# 06_KEY.net
KiCad netlist of a schematic drawn in Altium Designer
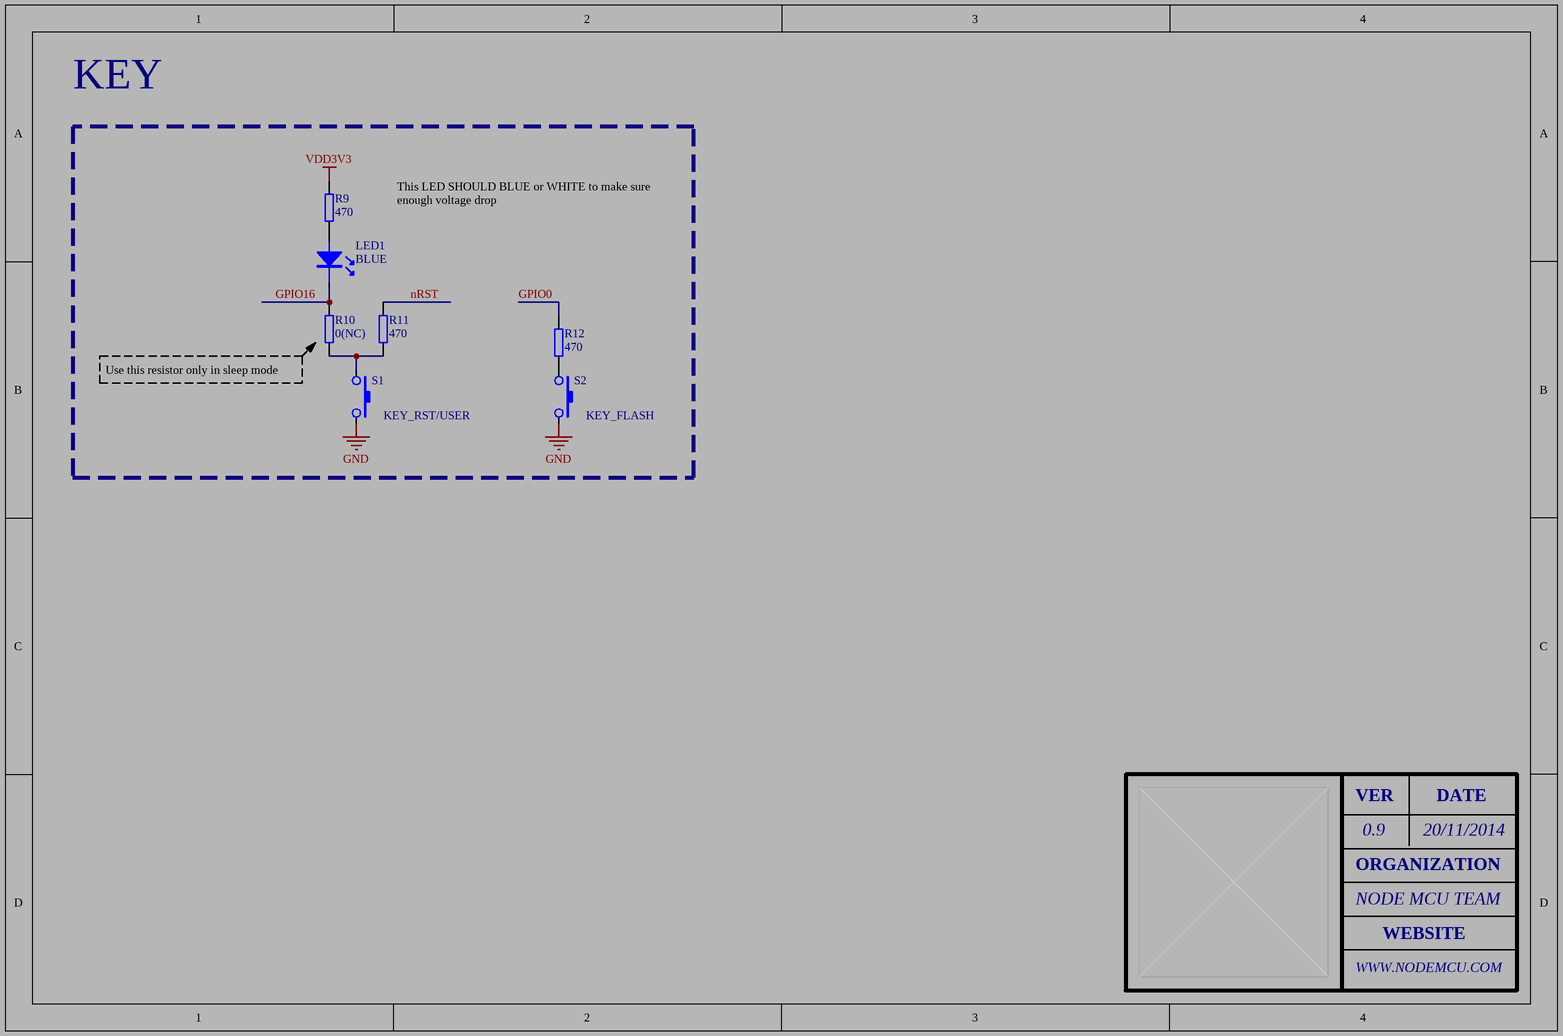
[diagram p0: 06_KEY.SchDoc]

(export (version "E")
  (design (tool "Eeschema 10.0.6"))
  (components
    (comp (ref "LED1")
      (value "BLUE")
      (footprint "SMT_LED_0603")
      (description "SMT LED")
      (libsource (lib "Vowstar_Basic_Device") (part "SMT_LED_0603"))
    )
    (comp (ref "R9")
      (value "470")
      (footprint "SMT_R_0402")
      (description "Surface mount resistor 0402")
      (libsource (lib "Vowstar_Basic_Device") (part "SMT_R_0402"))
    )
    (comp (ref "R10")
      (value "0(NC)")
      (footprint "SMT_R_0402")
      (description "Surface mount resistor 0402")
      (libsource (lib "Vowstar_Basic_Device") (part "SMT_R_0402"))
    )
    (comp (ref "R11")
      (value "470")
      (footprint "SMT_R_0402")
      (description "Surface mount resistor 0402")
      (libsource (lib "Vowstar_Basic_Device") (part "SMT_R_0402"))
    )
    (comp (ref "R12")
      (value "470")
      (footprint "SMT_R_0402")
      (description "Surface mount resistor 0402")
      (libsource (lib "Vowstar_Basic_Device") (part "SMT_R_0402"))
    )
    (comp (ref "S1")
      (value "KEY_RST/USER")
      (footprint "SMT_SW_PTS_820")
      (description "SMT Tactile ‎Switch PTS 820 Series")
      (libsource (lib "Vowstar_Switch") (part "SMT_SW_PTS_820"))
    )
    (comp (ref "S2")
      (value "KEY_FLASH")
      (footprint "SMT_SW_PTS_820")
      (description "SMT Tactile ‎Switch PTS 820 Series")
      (libsource (lib "Vowstar_Switch") (part "SMT_SW_PTS_820"))
    )
  )
  (nets
    (net (code "1") (name "/GPIO0") (class "Default")
      (node (ref "R12") (pin "2") (pinfunction "2_2") (pintype "passive"))
    )
    (net (code "2") (name "/GPIO16") (class "Default")
      (node (ref "LED1") (pin "2") (pinfunction "K_2") (pintype "passive"))
      (node (ref "R10") (pin "2") (pinfunction "2_2") (pintype "passive"))
    )
    (net (code "3") (name "/nRST") (class "Default")
      (node (ref "R11") (pin "2") (pinfunction "2_2") (pintype "passive"))
    )
    (net (code "4") (name "GND") (class "Default")
      (node (ref "S1") (pin "2") (pinfunction "2_2") (pintype "passive"))
      (node (ref "S2") (pin "2") (pinfunction "2_2") (pintype "passive"))
    )
    (net (code "5") (name "Net-(LED1-A)") (class "Default")
      (node (ref "LED1") (pin "1") (pinfunction "A_1") (pintype "passive"))
      (node (ref "R9") (pin "1") (pinfunction "1_1") (pintype "passive"))
    )
    (net (code "6") (name "Net-(R10-Pad1)") (class "Default")
      (node (ref "R10") (pin "1") (pinfunction "1_1") (pintype "passive"))
      (node (ref "R11") (pin "1") (pinfunction "1_1") (pintype "passive"))
      (node (ref "S1") (pin "1") (pinfunction "1_1") (pintype "passive"))
    )
    (net (code "7") (name "Net-(R12-Pad1)") (class "Default")
      (node (ref "R12") (pin "1") (pinfunction "1_1") (pintype "passive"))
      (node (ref "S2") (pin "1") (pinfunction "1_1") (pintype "passive"))
    )
    (net (code "8") (name "VDD3V3") (class "Default")
      (node (ref "R9") (pin "2") (pinfunction "2_2") (pintype "passive"))
    )
  )
)
